# Senkron_buck.net
KiCad netlist of a schematic drawn in Altium Designer
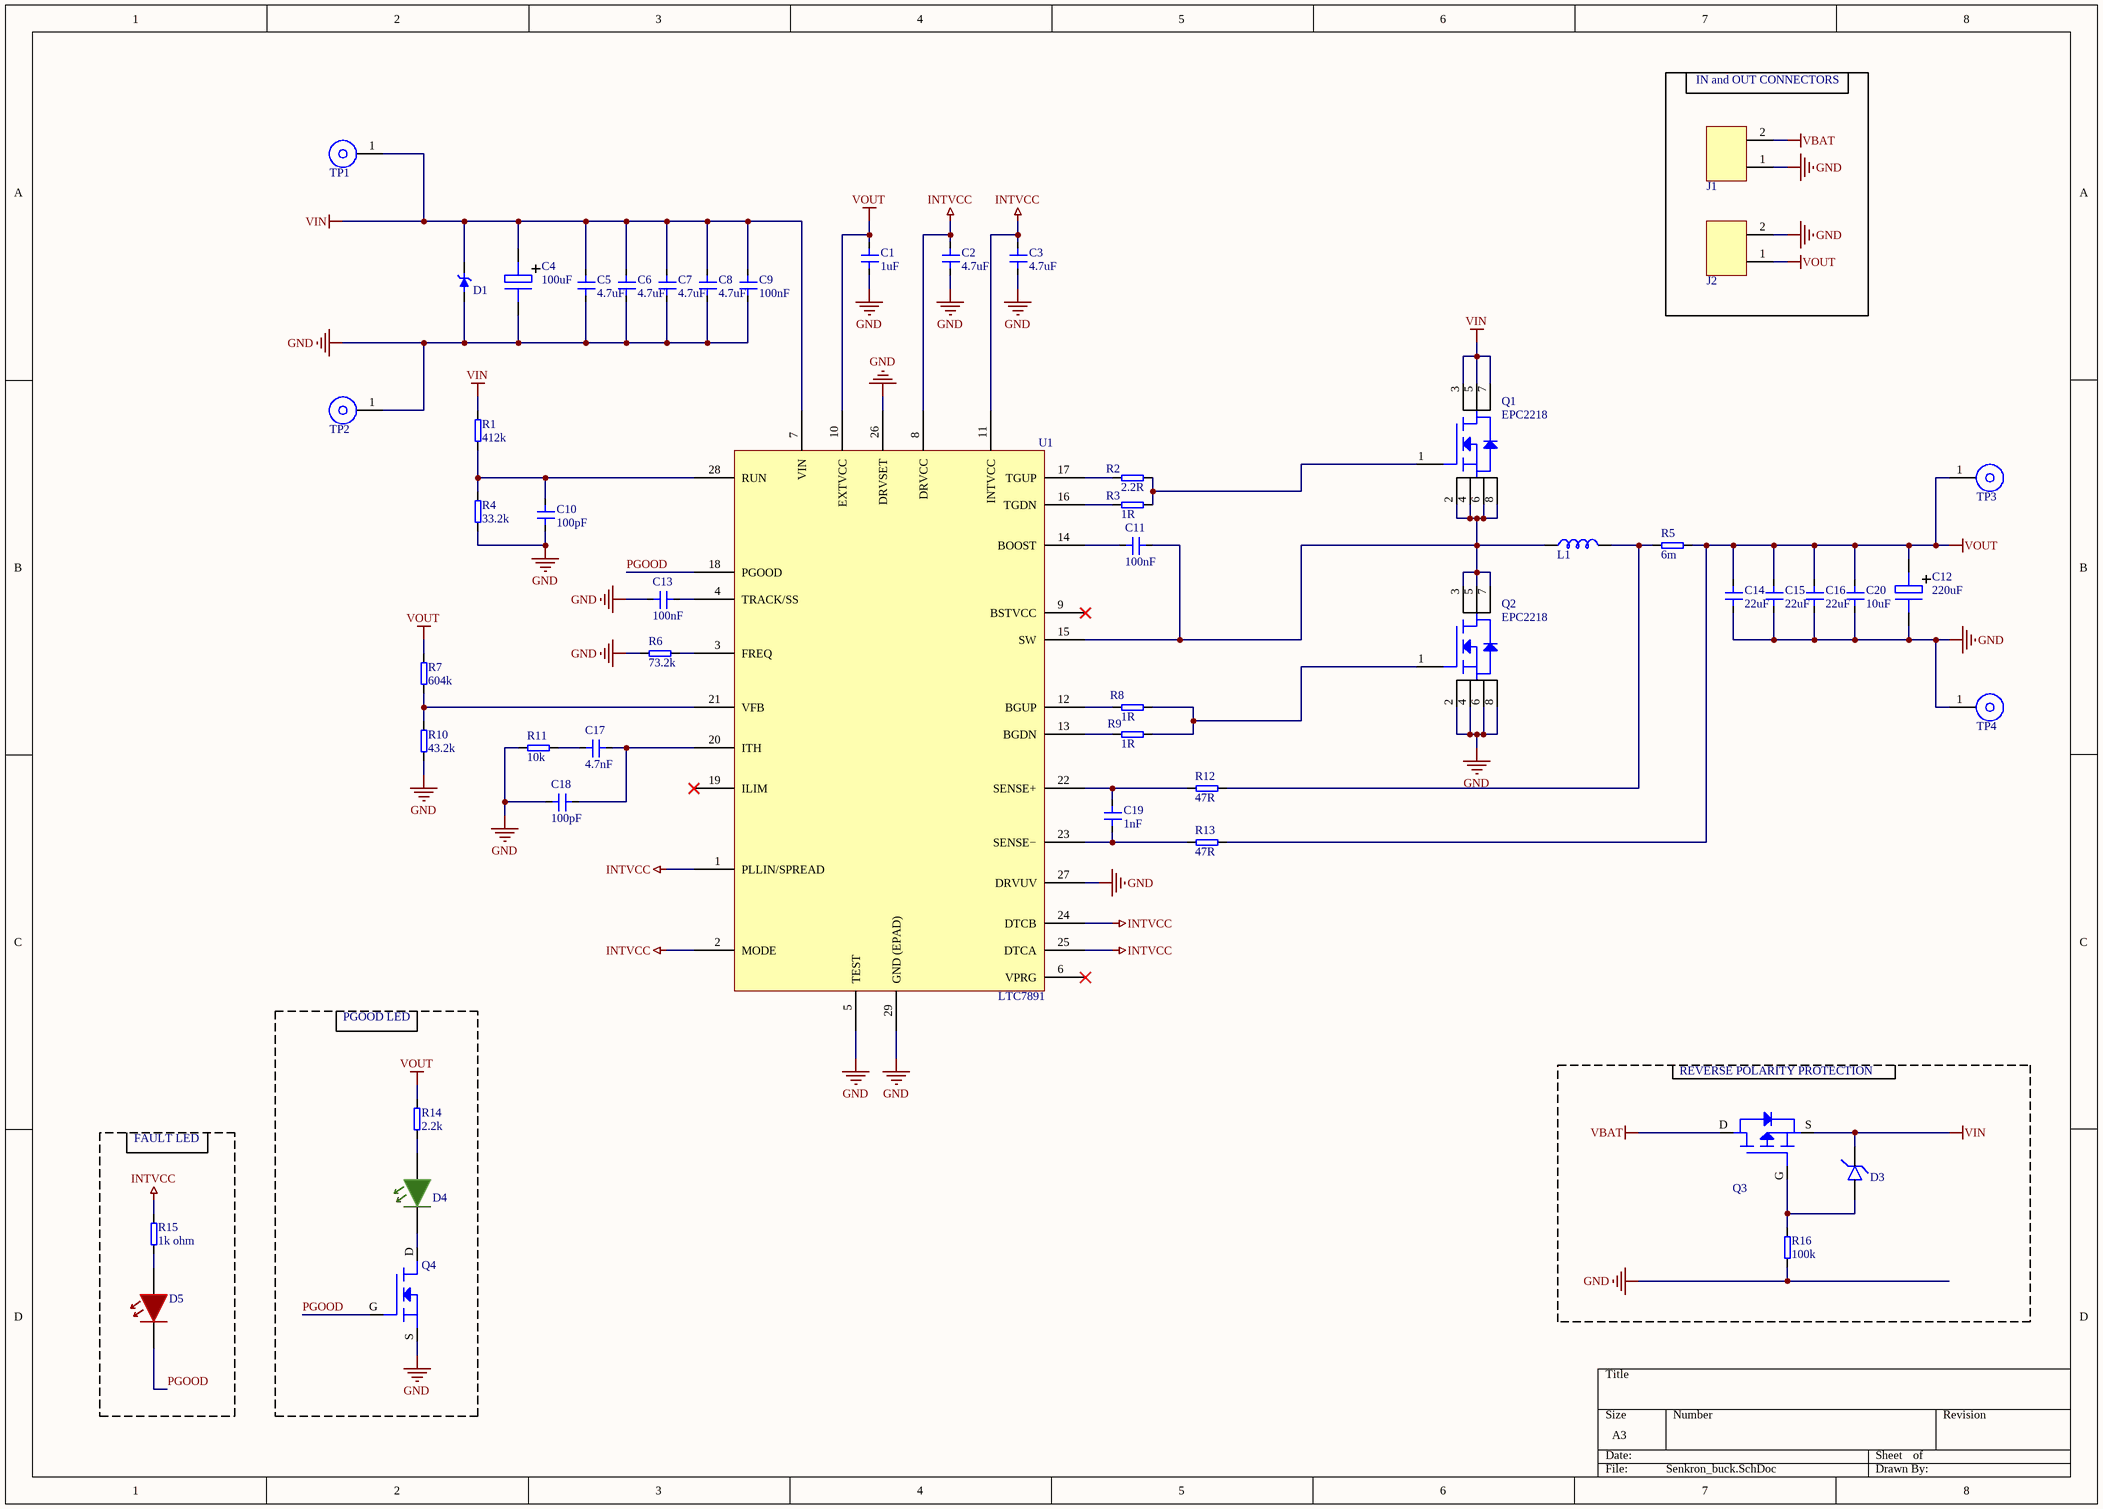
[diagram p0: Senkron_buck.SchDoc]

(export (version "E")
  (design (tool "Eeschema 10.0.6"))
  (components
    (comp (ref "C1")
      (value "1uF")
      (footprint "0603 CAP SER")
      (description "Multi Layer Ceramic Capacitor (MLCC) ¦ CAP CER 1UF 25V X7R 0603")
      (fields
        (field (name "MANUFACTURER") "Samsung Electro-Mechanics")
        (field (name "MANUFACTURER PART NUMBER") "CL10B105KA8NNNC")
      )
      (libsource (lib "Passive") (part "Cap Cer 1uF %10  SMD 0603"))
    )
    (comp (ref "C2")
      (value "4.7uF")
      (footprint "0603 CAP SER")
      (fields
        (field (name "MANUFACTURER") "Samsung Electro-Mechanics")
        (field (name "MANUFACTURER PART NUMBER") "CL10A475KO8NNNC")
        (field (name "TOLERANCE") "10%")
      )
      (libsource (lib "Passive") (part "Cap Cer 4.7uF %10 SMD 0603"))
    )
    (comp (ref "C3")
      (value "4.7uF")
      (footprint "0603 CAP SER")
      (fields
        (field (name "MANUFACTURER") "Samsung Electro-Mechanics")
        (field (name "MANUFACTURER PART NUMBER") "CL10A475KO8NNNC")
        (field (name "TOLERANCE") "10%")
      )
      (libsource (lib "Passive") (part "Cap Cer 4.7uF %10 SMD 0603"))
    )
    (comp (ref "C4")
      (value "100uF")
      (footprint "CAP ELEC 12.5X10")
      (description "CAP.EL.100uF 80V 10x12.5 105C 2000Hrs SMD")
      (libsource (lib "Passive") (part "Cap Elec 100uF 80V SMD"))
    )
    (comp (ref "C5")
      (value "4.7uF")
      (footprint "1210 CAP SER")
      (fields
        (field (name "MANUFACTURER") "Samsung Electro-Mechanics")
        (field (name "MANUFACTURER PART NUMBER") "CL32B475KBJNNNE")
        (field (name "TOLERANCE") "10%")
      )
      (libsource (lib "Passive") (part "Cap Cer 4.7uF %10 SMD 1210"))
    )
    (comp (ref "C6")
      (value "4.7uF")
      (footprint "1210 CAP SER")
      (fields
        (field (name "MANUFACTURER") "Samsung Electro-Mechanics")
        (field (name "MANUFACTURER PART NUMBER") "CL32B475KBJNNNE")
        (field (name "TOLERANCE") "10%")
      )
      (libsource (lib "Passive") (part "Cap Cer 4.7uF %10 SMD 1210"))
    )
    (comp (ref "C7")
      (value "4.7uF")
      (footprint "1210 CAP SER")
      (fields
        (field (name "MANUFACTURER") "Samsung Electro-Mechanics")
        (field (name "MANUFACTURER PART NUMBER") "CL32B475KBJNNNE")
        (field (name "TOLERANCE") "10%")
      )
      (libsource (lib "Passive") (part "Cap Cer 4.7uF %10 SMD 1210"))
    )
    (comp (ref "C8")
      (value "4.7uF")
      (footprint "1210 CAP SER")
      (fields
        (field (name "MANUFACTURER") "Samsung Electro-Mechanics")
        (field (name "MANUFACTURER PART NUMBER") "CL32B475KBJNNNE")
        (field (name "TOLERANCE") "10%")
      )
      (libsource (lib "Passive") (part "Cap Cer 4.7uF %10 SMD 1210"))
    )
    (comp (ref "C9")
      (value "100nF")
      (footprint "0603 CAP SER")
      (fields
        (field (name "MANUFACTURER") "KEMET")
        (field (name "MANUFACTURER PART NUMBER") "C0603C104J5RAC7867")
        (field (name "DESIGNED BY") "Eren/Mehmet")
      )
      (libsource (lib "Passive") (part "Cap Cer 0.1uF %10 SMD 0603"))
    )
    (comp (ref "C10")
      (value "100pF")
      (footprint "0603 CAP SER")
      (fields
        (field (name "MANUFACTURER") "Samsung Electro-Mechanics")
        (field (name "MANUFACTURER PART NUMBER") "CL10C101JB8NNNC")
        (field (name "TOLERANCE") "5%")
      )
      (libsource (lib "Passive") (part "Cap Cer 100pF %1 SMD 0603"))
    )
    (comp (ref "C11")
      (value "100nF")
      (footprint "0603 CAP SER")
      (fields
        (field (name "MANUFACTURER") "KEMET")
        (field (name "MANUFACTURER PART NUMBER") "C0603C104J5RAC7867")
        (field (name "DESIGNED BY") "Eren/Mehmet")
      )
      (libsource (lib "Passive") (part "Cap Cer 0.1uF %10 SMD 0603"))
    )
    (comp (ref "C12")
      (value "220uF")
      (footprint "CAP ELEC 10x10")
      (description "CAP.EL.220uF 50V 10x10 105C 2000Hrs SMD")
      (libsource (lib "Passive") (part "Cap Elec 220uF %20 50V SMD"))
    )
    (comp (ref "C13")
      (value "100nF")
      (footprint "0603 CAP SER")
      (fields
        (field (name "MANUFACTURER") "KEMET")
        (field (name "MANUFACTURER PART NUMBER") "C0603C104J5RAC7867")
        (field (name "DESIGNED BY") "Eren/Mehmet")
      )
      (libsource (lib "Passive") (part "Cap Cer 0.1uF %10 SMD 0603"))
    )
    (comp (ref "C14")
      (value "22uF")
      (footprint "1210 CAP SER")
      (description "25V 22uF X7R ±10% 1210 Multilayer Ceramic Capacitors MLCC - SMD/SMT ROHS")
      (fields
        (field (name "MANUFACTURER") "Samsung Electro-Mechanics")
        (field (name "MANUFACTURER PART NUMBER") "CL32B226KAJNNNE")
      )
      (libsource (lib "Passive") (part "Cap Cer 22uF %10 SMD 1210"))
    )
    (comp (ref "C15")
      (value "22uF")
      (footprint "1210 CAP SER")
      (description "25V 22uF X7R ±10% 1210 Multilayer Ceramic Capacitors MLCC - SMD/SMT ROHS")
      (fields
        (field (name "MANUFACTURER") "Samsung Electro-Mechanics")
        (field (name "MANUFACTURER PART NUMBER") "CL32B226KAJNNNE")
      )
      (libsource (lib "Passive") (part "Cap Cer 22uF %10 SMD 1210"))
    )
    (comp (ref "C16")
      (value "22uF")
      (footprint "1210 CAP SER")
      (description "25V 22uF X7R ±10% 1210 Multilayer Ceramic Capacitors MLCC - SMD/SMT ROHS")
      (fields
        (field (name "MANUFACTURER") "Samsung Electro-Mechanics")
        (field (name "MANUFACTURER PART NUMBER") "CL32B226KAJNNNE")
      )
      (libsource (lib "Passive") (part "Cap Cer 22uF %10 SMD 1210"))
    )
    (comp (ref "C17")
      (value "4.7nF")
      (footprint "0603 CAP SER")
      (fields
        (field (name "MANUFACTURER") "Samsung Electro-Mechanics")
        (field (name "MANUFACTURER PART NUMBER") "CL10B472KB8NNNC")
        (field (name "TOLERANCE") "10%")
      )
      (libsource (lib "Passive") (part "Cap Cer 4.7nF %10 SMD 0603"))
    )
    (comp (ref "C18")
      (value "100pF")
      (footprint "0603 CAP SER")
      (fields
        (field (name "MANUFACTURER") "Samsung Electro-Mechanics")
        (field (name "MANUFACTURER PART NUMBER") "CL10C101JB8NNNC")
        (field (name "TOLERANCE") "5%")
      )
      (libsource (lib "Passive") (part "Cap Cer 100pF %1 SMD 0603"))
    )
    (comp (ref "C19")
      (value "1nF")
      (footprint "0603 CAP SER")
      (fields
        (field (name "MANUFACTURER") "Samsung Electro-Mechanics")
        (field (name "MANUFACTURER PART NUMBER") "CL10B102KB8NNNC")
        (field (name "TOLERANCE") "10%")
      )
      (libsource (lib "Passive") (part "Cap Cer 1nF %10 SMD 0603"))
    )
    (comp (ref "C20")
      (value "10uF")
      (footprint "1206 CAP SER")
      (fields
        (field (name "MANUFACTURER") "Samsung Electro-Mechanics")
        (field (name "MANUFACTURER PART NUMBER") "CL31B106KAHNNNE")
        (field (name "TOLERANCE") "10%")
      )
      (libsource (lib "Passive") (part "Cap Cer 10uF %10 SMD 1206 (25V)"))
    )
    (comp (ref "D1")
      (value "SMAJ40A-HT")
      (footprint "DO-214AC SMA")
      (description "DO-214AC SMA SMAJ 1 Surface Mount Zener Tvs Diode 44.4V 5muA 400W -55C~150C TJ")
      (fields (field (name "MANUFACTURER") "HOTTECH"))
      (libsource (lib "Active") (part "DIODE TVS 400W 40V DO214AC SMA"))
    )
    (comp (ref "D3")
      (value "MMSZ15V-HT")
      (footprint "SOD-123")
      (description "DIODE ZENER 500mW 15V ±5% SOD123 SMT")
      (libsource (lib "Active") (part "MMSZ15V-HT"))
    )
    (comp (ref "D4")
      (value "LED SMD 0805 GREEN 18-45mcd 140° WATER CLEAR")
      (footprint "LED 0805 GREEN")
      (description "Single Color LED, Brilliant Yellow Green, Water Clear, 1.4mm")
      (fields
        (field (name "MANUFACTURER") "Everlight")
        (field (name "MANUFACTURER PART NUMBER") "17-21/G6C-FM1N2B/4T")
      )
      (libsource (lib "Active") (part "LED GREEN 0805"))
    )
    (comp (ref "D5")
      (value "LED SMD 0805 RED 45~112mcd 120C")
      (footprint "LED 0805 RED")
      (description "Single Color LED, Brilliant Red, Water Clear, 1.4mm")
      (fields
        (field (name "MANUFACTURER") "Everlight")
        (field (name "MANUFACTURER PART NUMBER") "17-21/R6C-AP1Q2L/4T")
      )
      (libsource (lib "Active") (part "LED RED 0805"))
    )
    (comp (ref "J1")
      (value "2P Screw Terminal Block 2 pin")
      (footprint "2P Screw Terminal Block 2 pin")
      (description "Barrier Strip Terminal Block, 13.5A, 1.5mm2, 1 Row(s), 1 Deck(s)")
      (fields
        (field (name "MANUFACTURER") "Phoenix Contact")
        (field (name "MANUFACTURER PART NUMBER") "1729128")
        (field (name "SAFETY APPROVAL") "CSA,CUL,CB,EAC")
      )
      (libsource (lib "Electromechanical") (part "2P Screw Terminal Block"))
    )
    (comp (ref "J2")
      (value "2P Screw Terminal Block 2 pin")
      (footprint "2P Screw Terminal Block 2 pin")
      (description "Barrier Strip Terminal Block, 13.5A, 1.5mm2, 1 Row(s), 1 Deck(s)")
      (fields
        (field (name "MANUFACTURER") "Phoenix Contact")
        (field (name "MANUFACTURER PART NUMBER") "1729128")
        (field (name "SAFETY APPROVAL") "CSA,CUL,CB,EAC")
      )
      (libsource (lib "Electromechanical") (part "2P Screw Terminal Block"))
    )
    (comp (ref "L1")
      (value "10 µH Shielded Drum Core, Wirewound Inductor 21 A 3.4mOhm Nonstandard")
      (footprint "74435581000 INDUCTOR")
      (description "WE-HCI SMT Flat Wire High Current Inductor")
      (fields
        (field (name "MANUFACTURER") "Wurth Elektronik")
        (field (name "MANUFACTURER PART NUMBER") "74435581000")
      )
      (libsource (lib "Passive") (part "Inductor 10uH %20 SMD NONSTANDART 3.4mOhm"))
    )
    (comp (ref "Q1")
      (value "EPC2218")
      (footprint "EPC2218")
      (description "N-Channel 100 V 60A (Ta) Surface Mount Die")
      (libsource (lib "Active") (part "EPC2218"))
    )
    (comp (ref "Q2")
      (value "EPC2218")
      (footprint "EPC2218")
      (description "N-Channel 100 V 60A (Ta) Surface Mount Die")
      (libsource (lib "Active") (part "EPC2218"))
    )
    (comp (ref "Q3")
      (value "MOSFET DIS.52A 60V P-CH POWERPAKSO-8")
      (footprint "PowerPAK® SO-8L SINGLE")
      (description "SQJ459EP Series -60 V 0.024 Ohm Automotive P-Channel Mosfet - PowerPAK SO-8L")
      (fields
        (field (name "MANUFACTURER") "Vishay")
        (field (name "MANUFACTURER PART NUMBER") "SQJ459EP-T1_GE3")
      )
      (libsource (lib "Active") (part "SQJ459EP-T1_GE3"))
    )
    (comp (ref "Q4")
      (value "PJA3416AE_R1_00001")
      (footprint "SOT-23 MOSFET")
      (description "MOSFET DIS.6.5A 20V N-CH SOT23 SMT")
      (fields (field (name "MANUFACTURER") "Pan Jit") (field (name "DESIGNED BY") "Eren/Mehmet"))
      (libsource (lib "Active") (part "PJA3416AE_R1_00001"))
    )
    (comp (ref "R1")
      (value "412k")
      (footprint "0805 RES")
      (description "RES.(2012) 0805 412K Ohms 1% 1/8W-S 100PPM")
      (fields
        (field (name "MANUFACTURER") "Royal Ohm")
        (field (name "MANUFACTURER PART NUMBER") "0805S8F4123T5E")
      )
      (libsource (lib "Passive") (part "RES 412k Ohm %1 SMD 0805"))
    )
    (comp (ref "R2")
      (value "2.2R")
      (footprint "0603 RES")
      (description "RES.(1608) 0603 2.2 Ohms 1% 1/10W AUTOMOTIV")
      (fields
        (field (name "MANUFACTURER") "Royal Ohm")
        (field (name "MANUFACTURER PART NUMBER") "CQ03SAF220KT5E")
      )
      (libsource (lib "Passive") (part "RES 2.2R Ohm %1 SMD 0603_1"))
    )
    (comp (ref "R3")
      (value "1R")
      (footprint "0603 RES")
      (description "RES.(1608) 0603 1 Ohms 1% 1/10W AUTOMOTIV")
      (fields
        (field (name "MANUFACTURER") "Royal Ohm")
        (field (name "MANUFACTURER PART NUMBER") "CQ03SAF100KT5E")
      )
      (libsource (lib "Passive") (part "RES 1R Ohm %1 SMD 0603"))
    )
    (comp (ref "R4")
      (value "33.2k")
      (footprint "0805 RES")
      (description "RES.(2012) 0805 33.2K Ohms 1% 1/8W-S 100PPM")
      (fields
        (field (name "MANUFACTURER") "Royal Ohm")
        (field (name "MANUFACTURER PART NUMBER") "0805S8F3322T5E")
      )
      (libsource (lib "Passive") (part "RES 33.2k Ohm %1 SMD 0805"))
    )
    (comp (ref "R5")
      (value "6m")
      (footprint "1206 RES")
      (description "RES.(3216) 1206 6m Ohms 1% 1W 50PPM")
      (libsource (lib "Passive") (part "RES 6m Ohm %1 SMD 1206"))
    )
    (comp (ref "R6")
      (value "73.2k")
      (footprint "0603 RES")
      (description "RES.(1608) 0603 73.2K Ohms 1% 1/10W-S 100PPM")
      (fields
        (field (name "MANUFACTURER") "Royal Ohm")
        (field (name "MANUFACTURER PART NUMBER") "0603SAF7322T5E")
      )
      (libsource (lib "Passive") (part "RES 73.2k Ohm %1 SMD 0603"))
    )
    (comp (ref "R7")
      (value "604k")
      (footprint "0805 RES")
      (description "RES.(2012) 0805 604K Ohms 1% 1/8W-S 100PPM")
      (fields
        (field (name "MANUFACTURER") "Royal Ohm")
        (field (name "MANUFACTURER PART NUMBER") "0805S8F6043T5E")
      )
      (libsource (lib "Passive") (part "RES 604k Ohm %1 SMD 0805"))
    )
    (comp (ref "R8")
      (value "1R")
      (footprint "0603 RES")
      (description "RES.(1608) 0603 1 Ohms 1% 1/10W AUTOMOTIV")
      (fields
        (field (name "MANUFACTURER") "Royal Ohm")
        (field (name "MANUFACTURER PART NUMBER") "CQ03SAF100KT5E")
      )
      (libsource (lib "Passive") (part "RES 1R Ohm %1 SMD 0603"))
    )
    (comp (ref "R9")
      (value "1R")
      (footprint "0603 RES")
      (description "RES.(1608) 0603 1 Ohms 1% 1/10W AUTOMOTIV")
      (fields
        (field (name "MANUFACTURER") "Royal Ohm")
        (field (name "MANUFACTURER PART NUMBER") "CQ03SAF100KT5E")
      )
      (libsource (lib "Passive") (part "RES 1R Ohm %1 SMD 0603"))
    )
    (comp (ref "R10")
      (value "43.2k")
      (footprint "0805 RES")
      (description "RES.(2012) 0805 43.2K Ohms 1% 1/8W-S 100PPM")
      (fields
        (field (name "MANUFACTURER") "Royal Ohm")
        (field (name "MANUFACTURER PART NUMBER") "0805S8F4322T5E")
      )
      (libsource (lib "Passive") (part "RES 43.2k Ohm %1 SMD 0805"))
    )
    (comp (ref "R11")
      (value "10k")
      (footprint "0603 RES")
      (description "100mW Thick Film Resistors ±100ppm/℃ ±1% 10kΩ 0603 Chip Resistor - Surface Mount ROHS")
      (fields
        (field (name "MANUFACTURER") "Yageo Group")
        (field (name "MANUFACTURER PART NUMBER") "RC0603FR-0710KL")
      )
      (libsource (lib "Passive") (part "RES 10kOhm %1 SMD 0603"))
    )
    (comp (ref "R12")
      (value "47R")
      (footprint "0603 RES")
      (description "RES.(1608) 0603 47 Ohms 1% 1/10W AUTOMOTIV")
      (fields
        (field (name "MANUFACTURER") "Royal Ohm")
        (field (name "MANUFACTURER PART NUMBER") "CQ03SAF470JT5E")
      )
      (libsource (lib "Passive") (part "RES 47R Ohm %1 SMD 0603"))
    )
    (comp (ref "R13")
      (value "47R")
      (footprint "0603 RES")
      (description "RES.(1608) 0603 47 Ohms 1% 1/10W AUTOMOTIV")
      (fields
        (field (name "MANUFACTURER") "Royal Ohm")
        (field (name "MANUFACTURER PART NUMBER") "CQ03SAF470JT5E")
      )
      (libsource (lib "Passive") (part "RES 47R Ohm %1 SMD 0603"))
    )
    (comp (ref "R14")
      (value "2.2k")
      (footprint "0603 RES")
      (description "Res Thick Film 0603 2.2K Ohm 1% 0.1W(1/10W) +/-100ppm/C Epoxy Pad SMD T/R")
      (fields
        (field (name "MANUFACTURER") "Yageo Group")
        (field (name "MANUFACTURER PART NUMBER") "RC0603FR-072K2L")
      )
      (libsource (lib "Passive") (part "RES 2.2k Ohm %1 SMD 0603"))
    )
    (comp (ref "R15")
      (value "1k ohm")
      (footprint "0603 RES")
      (fields
        (field (name "MANUFACTURER") "Yageo")
        (field (name "MANUFACTURER PART NUMBER") "RC0603JR-071KL")
        (field (name "TOLERANCE") "5%")
        (field (name "DESIGNED BY") "Eren/Mehmet")
      )
      (libsource (lib "Passive") (part "RES 1kOhm %5 SMD 0603"))
    )
    (comp (ref "R16")
      (value "100k")
      (footprint "0603 RES")
      (fields
        (field (name "MANUFACTURER") "Yageo")
        (field (name "MANUFACTURER PART NUMBER") "RC0603JR-07100KL")
        (field (name "TOLERANCE") "5%")
        (field (name "DESIGNED BY") "Eren/Mehmet")
      )
      (libsource (lib "Passive") (part "RES 100kOhm %5 SMD 0603"))
    )
    (comp (ref "TP1")
      (value "Test Point")
      (footprint "Test Point THT")
      (description "PC TEST POINT MINIATURE BLACK 2.54MMX4.60MM")
      (libsource (lib "Electromechanical") (part "Test Point THT"))
    )
    (comp (ref "TP2")
      (value "Test Point")
      (footprint "Test Point THT")
      (description "PC TEST POINT MINIATURE BLACK 2.54MMX4.60MM")
      (libsource (lib "Electromechanical") (part "Test Point THT"))
    )
    (comp (ref "TP3")
      (value "Test Point")
      (footprint "Test Point THT")
      (description "PC TEST POINT MINIATURE BLACK 2.54MMX4.60MM")
      (libsource (lib "Electromechanical") (part "Test Point THT"))
    )
    (comp (ref "TP4")
      (value "Test Point")
      (footprint "Test Point THT")
      (description "PC TEST POINT MINIATURE BLACK 2.54MMX4.60MM")
      (libsource (lib "Electromechanical") (part "Test Point THT"))
    )
    (comp (ref "U1")
      (value "LTC7891")
      (footprint "28-Lead Plastic Side Wettable QFN (4mm × 5mm)")
      (description "DC/DC Cntrlr Single-OUT Step Down 3000kHz 28-Pin QFN EP Tube")
      (fields
        (field (name "MANUFACTURER") "Analog Devices")
        (field (name "MANUFACTURER PART NUMBER") "LTC7891RUFDM#PBF")
      )
      (libsource (lib "Integrated Circuits - IC") (part "LTC7891"))
    )
  )
  (nets
    (net (code "1") (name "/PGOOD") (class "Default")
      (node (ref "D5") (pin "2") (pinfunction "2_2") (pintype "power_in"))
      (node (ref "Q4") (pin "G") (pintype "passive"))
      (node (ref "U1") (pin "18") (pinfunction "PGOOD_18") (pintype "passive"))
    )
    (net (code "2") (name "GND") (class "Default")
      (node (ref "C1") (pin "1") (pintype "passive"))
      (node (ref "C10") (pin "1") (pintype "passive"))
      (node (ref "C12") (pin "2") (pintype "passive"))
      (node (ref "C13") (pin "1") (pintype "passive"))
      (node (ref "C14") (pin "1") (pintype "passive"))
      (node (ref "C15") (pin "1") (pintype "passive"))
      (node (ref "C16") (pin "1") (pintype "passive"))
      (node (ref "C18") (pin "1") (pintype "passive"))
      (node (ref "C2") (pin "1") (pintype "passive"))
      (node (ref "C20") (pin "1") (pintype "passive"))
      (node (ref "C3") (pin "1") (pintype "passive"))
      (node (ref "C4") (pin "2") (pintype "passive"))
      (node (ref "C5") (pin "1") (pintype "passive"))
      (node (ref "C6") (pin "1") (pintype "passive"))
      (node (ref "C7") (pin "1") (pintype "passive"))
      (node (ref "C8") (pin "1") (pintype "passive"))
      (node (ref "C9") (pin "1") (pintype "passive"))
      (node (ref "D1") (pin "A") (pinfunction "1_A") (pintype "passive"))
      (node (ref "J1") (pin "1") (pinfunction "1_1") (pintype "passive"))
      (node (ref "J2") (pin "2") (pinfunction "2_2") (pintype "passive"))
      (node (ref "Q2") (pin "2") (pinfunction "2_2") (pintype "passive"))
      (node (ref "Q2") (pin "4") (pinfunction "4_4") (pintype "passive"))
      (node (ref "Q2") (pin "6") (pinfunction "6_6") (pintype "passive"))
      (node (ref "Q2") (pin "8") (pinfunction "8_8") (pintype "passive"))
      (node (ref "Q4") (pin "S") (pintype "passive"))
      (node (ref "R10") (pin "1") (pintype "passive"))
      (node (ref "R11") (pin "1") (pintype "passive"))
      (node (ref "R16") (pin "1") (pintype "passive"))
      (node (ref "R4") (pin "1") (pintype "passive"))
      (node (ref "R6") (pin "1") (pintype "passive"))
      (node (ref "TP2") (pin "1") (pinfunction "1_1") (pintype "passive"))
      (node (ref "TP4") (pin "1") (pinfunction "1_1") (pintype "passive"))
      (node (ref "U1") (pin "26") (pinfunction "DRVSET_26") (pintype "passive"))
      (node (ref "U1") (pin "27") (pinfunction "DRVUV_27") (pintype "passive"))
      (node (ref "U1") (pin "29") (pinfunction "GND_(EPAD)_29") (pintype "passive"))
      (node (ref "U1") (pin "5") (pinfunction "TEST_5") (pintype "passive"))
    )
    (net (code "3") (name "INTVCC") (class "Default")
      (node (ref "C2") (pin "2") (pintype "passive"))
      (node (ref "C3") (pin "2") (pintype "passive"))
      (node (ref "R15") (pin "2") (pintype "passive"))
      (node (ref "U1") (pin "1") (pinfunction "PLLIN/SPREAD_1") (pintype "passive"))
      (node (ref "U1") (pin "11") (pinfunction "INTVCC_11") (pintype "passive"))
      (node (ref "U1") (pin "2") (pinfunction "MODE_2") (pintype "passive"))
      (node (ref "U1") (pin "24") (pinfunction "DTCB_24") (pintype "passive"))
      (node (ref "U1") (pin "25") (pinfunction "DTCA_25") (pintype "passive"))
      (node (ref "U1") (pin "8") (pinfunction "DRVCC_8") (pintype "passive"))
    )
    (net (code "4") (name "Net-(C17-Pad1)") (class "Default")
      (node (ref "C17") (pin "1") (pintype "passive"))
      (node (ref "R11") (pin "2") (pintype "passive"))
    )
    (net (code "5") (name "Net-(D3-Anot)") (class "Default")
      (node (ref "D3") (pin "A") (pinfunction "Anot_A") (pintype "passive"))
      (node (ref "Q3") (pin "G") (pintype "passive"))
      (node (ref "R16") (pin "2") (pintype "passive"))
    )
    (net (code "6") (name "Net-(D4-Pad1)") (class "Default")
      (node (ref "D4") (pin "1") (pinfunction "1_1") (pintype "power_in"))
      (node (ref "R14") (pin "1") (pintype "passive"))
    )
    (net (code "7") (name "Net-(D4-Pad2)") (class "Default")
      (node (ref "D4") (pin "2") (pinfunction "2_2") (pintype "power_in"))
      (node (ref "Q4") (pin "D") (pintype "passive"))
    )
    (net (code "8") (name "Net-(D5-Pad1)") (class "Default")
      (node (ref "D5") (pin "1") (pinfunction "1_1") (pintype "power_in"))
      (node (ref "R15") (pin "1") (pintype "passive"))
    )
    (net (code "9") (name "Net-(L1-Pad2)") (class "Default")
      (node (ref "L1") (pin "2") (pinfunction "2_2") (pintype "passive"))
      (node (ref "R12") (pin "2") (pintype "passive"))
      (node (ref "R5") (pin "1") (pintype "passive"))
    )
    (net (code "10") (name "Net-(Q1-Pad1)") (class "Default")
      (node (ref "Q1") (pin "1") (pinfunction "1_1") (pintype "passive"))
      (node (ref "R2") (pin "2") (pintype "passive"))
      (node (ref "R3") (pin "2") (pintype "passive"))
    )
    (net (code "11") (name "Net-(Q2-Pad1)") (class "Default")
      (node (ref "Q2") (pin "1") (pinfunction "1_1") (pintype "passive"))
      (node (ref "R8") (pin "2") (pintype "passive"))
      (node (ref "R9") (pin "2") (pintype "passive"))
    )
    (net (code "12") (name "Net-(U1-BGDN)") (class "Default")
      (node (ref "R9") (pin "1") (pintype "passive"))
      (node (ref "U1") (pin "13") (pinfunction "BGDN_13") (pintype "passive"))
    )
    (net (code "13") (name "Net-(U1-BGUP)") (class "Default")
      (node (ref "R8") (pin "1") (pintype "passive"))
      (node (ref "U1") (pin "12") (pinfunction "BGUP_12") (pintype "passive"))
    )
    (net (code "14") (name "Net-(U1-BOOST)") (class "Default")
      (node (ref "C11") (pin "1") (pintype "passive"))
      (node (ref "U1") (pin "14") (pinfunction "BOOST_14") (pintype "passive"))
    )
    (net (code "15") (name "Net-(U1-FREQ)") (class "Default")
      (node (ref "R6") (pin "2") (pintype "passive"))
      (node (ref "U1") (pin "3") (pinfunction "FREQ_3") (pintype "passive"))
    )
    (net (code "16") (name "Net-(U1-ITH)") (class "Default")
      (node (ref "C17") (pin "2") (pintype "passive"))
      (node (ref "C18") (pin "2") (pintype "passive"))
      (node (ref "U1") (pin "20") (pinfunction "ITH_20") (pintype "passive"))
    )
    (net (code "17") (name "Net-(U1-RUN)") (class "Default")
      (node (ref "C10") (pin "2") (pintype "passive"))
      (node (ref "R1") (pin "1") (pintype "passive"))
      (node (ref "R4") (pin "2") (pintype "passive"))
      (node (ref "U1") (pin "28") (pinfunction "RUN_28") (pintype "passive"))
    )
    (net (code "18") (name "Net-(U1-SENSE+)") (class "Default")
      (node (ref "C19") (pin "2") (pintype "passive"))
      (node (ref "R12") (pin "1") (pintype "passive"))
      (node (ref "U1") (pin "22") (pinfunction "SENSE+_22") (pintype "passive"))
    )
    (net (code "19") (name "Net-(U1-SENSE−)") (class "Default")
      (node (ref "C19") (pin "1") (pintype "passive"))
      (node (ref "R13") (pin "1") (pintype "passive"))
      (node (ref "U1") (pin "23") (pinfunction "SENSE−_23") (pintype "passive"))
    )
    (net (code "20") (name "Net-(U1-SW)") (class "Default")
      (node (ref "C11") (pin "2") (pintype "passive"))
      (node (ref "L1") (pin "1") (pinfunction "1_1") (pintype "passive"))
      (node (ref "Q1") (pin "2") (pinfunction "2_2") (pintype "passive"))
      (node (ref "Q1") (pin "4") (pinfunction "4_4") (pintype "passive"))
      (node (ref "Q1") (pin "6") (pinfunction "6_6") (pintype "passive"))
      (node (ref "Q1") (pin "8") (pinfunction "8_8") (pintype "passive"))
      (node (ref "Q2") (pin "3") (pinfunction "3_3") (pintype "passive"))
      (node (ref "Q2") (pin "5") (pinfunction "5_5") (pintype "passive"))
      (node (ref "Q2") (pin "7") (pinfunction "7_7") (pintype "passive"))
      (node (ref "U1") (pin "15") (pinfunction "SW_15") (pintype "passive"))
    )
    (net (code "21") (name "Net-(U1-TGDN)") (class "Default")
      (node (ref "R3") (pin "1") (pintype "passive"))
      (node (ref "U1") (pin "16") (pinfunction "TGDN_16") (pintype "passive"))
    )
    (net (code "22") (name "Net-(U1-TGUP)") (class "Default")
      (node (ref "R2") (pin "1") (pintype "passive"))
      (node (ref "U1") (pin "17") (pinfunction "TGUP_17") (pintype "passive"))
    )
    (net (code "23") (name "Net-(U1-TRACK{slash}SS)") (class "Default")
      (node (ref "C13") (pin "2") (pintype "passive"))
      (node (ref "U1") (pin "4") (pinfunction "TRACK/SS_4") (pintype "passive"))
    )
    (net (code "24") (name "Net-(U1-VFB)") (class "Default")
      (node (ref "R10") (pin "2") (pintype "passive"))
      (node (ref "R7") (pin "1") (pintype "passive"))
      (node (ref "U1") (pin "21") (pinfunction "VFB_21") (pintype "passive"))
    )
    (net (code "25") (name "VBAT") (class "Default")
      (node (ref "J1") (pin "2") (pinfunction "2_2") (pintype "passive"))
      (node (ref "Q3") (pin "D") (pinfunction "D_D") (pintype "passive"))
    )
    (net (code "26") (name "VIN") (class "Default")
      (node (ref "C4") (pin "1") (pintype "passive"))
      (node (ref "C5") (pin "2") (pintype "passive"))
      (node (ref "C6") (pin "2") (pintype "passive"))
      (node (ref "C7") (pin "2") (pintype "passive"))
      (node (ref "C8") (pin "2") (pintype "passive"))
      (node (ref "C9") (pin "2") (pintype "passive"))
      (node (ref "D1") (pin "K") (pinfunction "2_K") (pintype "passive"))
      (node (ref "D3") (pin "K") (pinfunction "Katot_K") (pintype "passive"))
      (node (ref "Q1") (pin "3") (pinfunction "3_3") (pintype "passive"))
      (node (ref "Q1") (pin "5") (pinfunction "5_5") (pintype "passive"))
      (node (ref "Q1") (pin "7") (pinfunction "7_7") (pintype "passive"))
      (node (ref "Q3") (pin "S") (pinfunction "S_S") (pintype "passive"))
      (node (ref "R1") (pin "2") (pintype "passive"))
      (node (ref "TP1") (pin "1") (pinfunction "1_1") (pintype "passive"))
      (node (ref "U1") (pin "7") (pinfunction "VIN_7") (pintype "passive"))
    )
    (net (code "27") (name "VOUT") (class "Default")
      (node (ref "C1") (pin "2") (pintype "passive"))
      (node (ref "C12") (pin "1") (pintype "passive"))
      (node (ref "C14") (pin "2") (pintype "passive"))
      (node (ref "C15") (pin "2") (pintype "passive"))
      (node (ref "C16") (pin "2") (pintype "passive"))
      (node (ref "C20") (pin "2") (pintype "passive"))
      (node (ref "J2") (pin "1") (pinfunction "1_1") (pintype "passive"))
      (node (ref "R13") (pin "2") (pintype "passive"))
      (node (ref "R14") (pin "2") (pintype "passive"))
      (node (ref "R5") (pin "2") (pintype "passive"))
      (node (ref "R7") (pin "2") (pintype "passive"))
      (node (ref "TP3") (pin "1") (pinfunction "1_1") (pintype "passive"))
      (node (ref "U1") (pin "10") (pinfunction "EXTVCC_10") (pintype "passive"))
    )
    (net (code "28") (name "unconnected-(U1-BSTVCC-Pad9)") (class "Default")
      (node (ref "U1") (pin "9") (pinfunction "BSTVCC_9") (pintype "passive+no_connect"))
    )
    (net (code "29") (name "unconnected-(U1-ILIM-Pad19)") (class "Default")
      (node (ref "U1") (pin "19") (pinfunction "ILIM_19") (pintype "passive+no_connect"))
    )
    (net (code "30") (name "unconnected-(U1-VPRG-Pad6)") (class "Default")
      (node (ref "U1") (pin "6") (pinfunction "VPRG_6") (pintype "passive+no_connect"))
    )
  )
)
